# Peripherals.net
KiCad netlist of a schematic drawn in Altium Designer
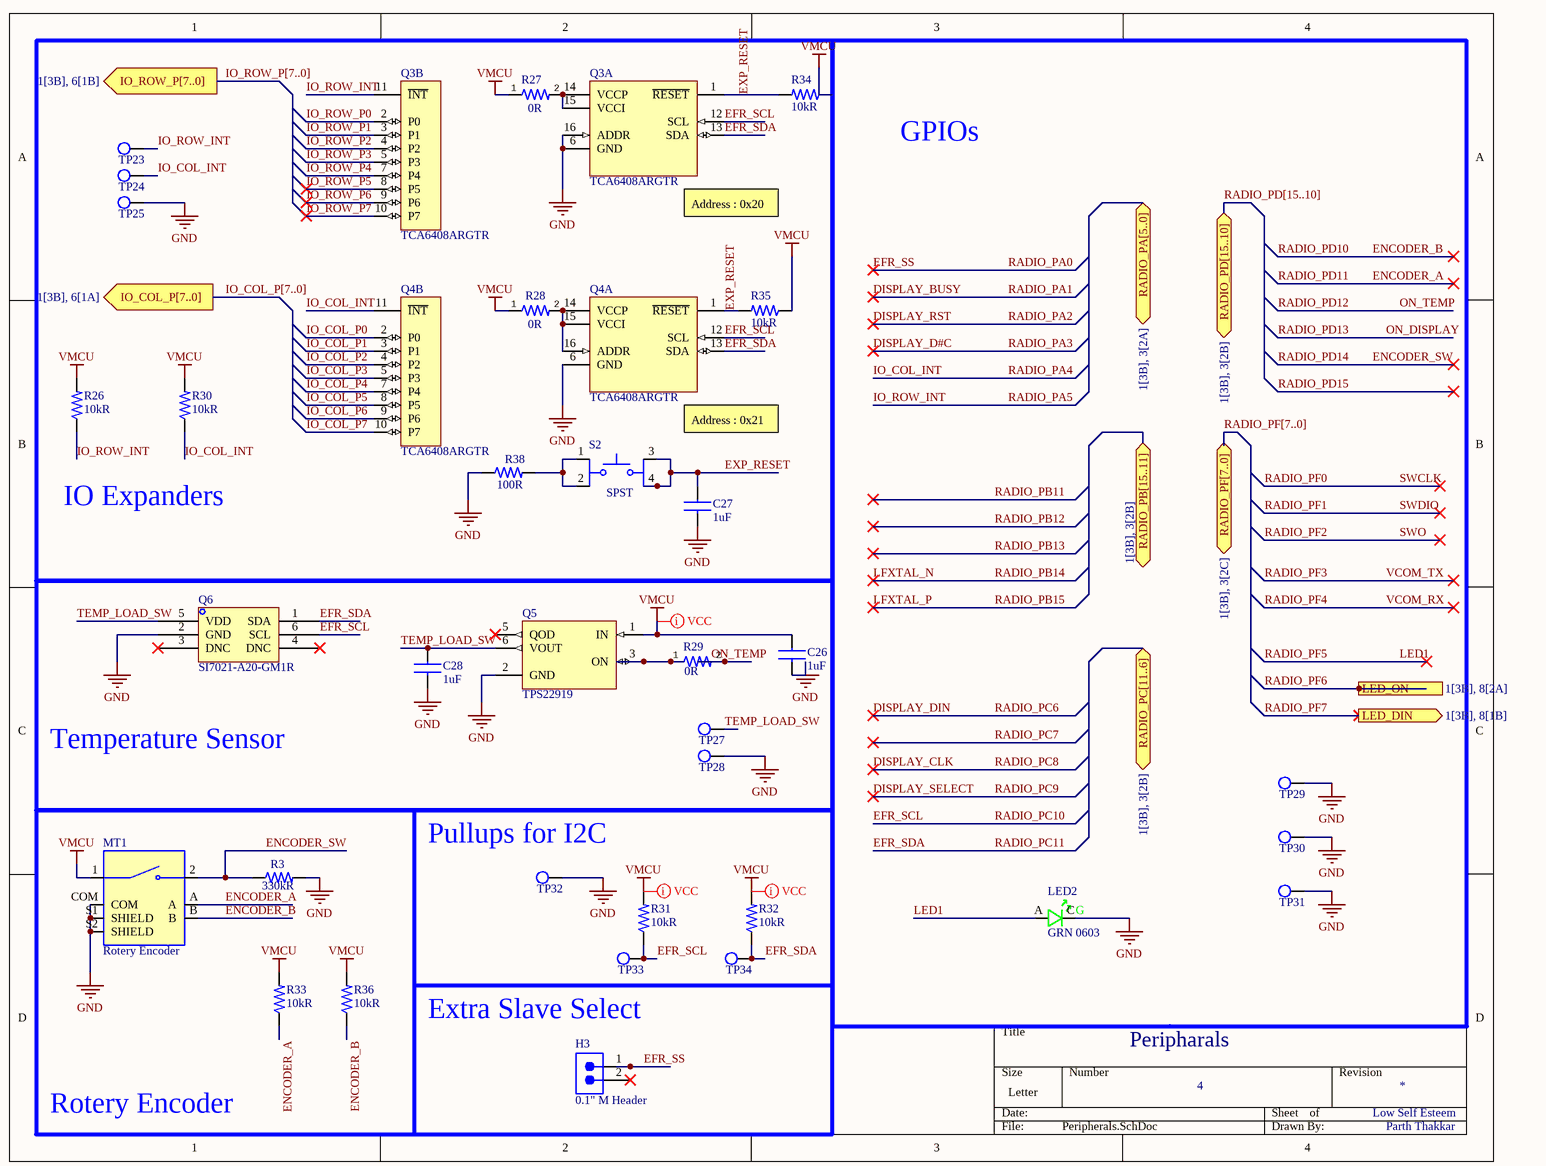
[diagram p0: Peripherals.SchDoc]

(export (version "E")
  (design (tool "Eeschema 10.0.6"))
  (components
    (comp (ref "C26")
      (value "1uF")
      (footprint "Capacitor 0603")
      (fields
        (field (name "MANUFACTURER") "Murata")
        (field (name "MANUFACTURER PART NUMBER") "GRM188R61A105KA61D")
        (field (name "Comment") "CAP 1uF 10V 0603")
      )
      (libsource (lib "Keyboard_parts") (part "CAP 1uF 10V 0603"))
    )
    (comp (ref "C27")
      (value "1uF")
      (footprint "Capacitor 0603")
      (fields
        (field (name "MANUFACTURER") "Murata")
        (field (name "MANUFACTURER PART NUMBER") "GRM188R61A105KA61D")
        (field (name "Comment") "CAP 1uF 10V 0603")
      )
      (libsource (lib "Keyboard_parts") (part "CAP 1uF 10V 0603"))
    )
    (comp (ref "C28")
      (value "1uF")
      (footprint "CAPACITOR 0805")
      (description "Multilayer Ceramic Capacitor, 1 uF, 10 V, ± 20%, X5R, 0201 [0603 Metric]")
      (fields
        (field (name "MANUFACTURER") "Murata")
        (field (name "MANUFACTURER PART NUMBER") "GRM033R61A105ME15D")
      )
      (libsource (lib "Keyboard_parts") (part "CAP 47uF 10V 0805"))
    )
    (comp (ref "H3")
      (value "0.1\" M Header")
      (footprint "2-PIN_MALE_HEADER_01-IN")
      (description "CONN HEADER VERT 2POS 2.54MM")
      (fields
        (field (name "MANUFACTURER") "Sullins")
        (field (name "MANUFACTURER PART NUMBER") "PRPC002SAAN-RC")
      )
      (libsource (lib "InsaneIntegratedLib") (part "PRPC002SAAN-RC"))
    )
    (comp (ref "LED2")
      (value "GRN 0603")
      (footprint "LED 0603")
      (description "LED, 0603, GREEN, 430MCD, 520NM")
      (fields
        (field (name "MANUFACTURER") "Wurth Electronics")
        (field (name "MANUFACTURER PART NUMBER") "150060GS75000")
      )
      (libsource (lib "InsaneIntegratedLib") (part "LED Green 0603"))
    )
    (comp (ref "MT1")
      (value "Rotery Encoder")
      (footprint "Rotery Encoder")
      (description "Rotary Position Encoder, Single, 2 Channels")
      (fields (field (name "MP") "PEC11R-4215F-S0024") (field (name "MANUFACTURER") "Bourns"))
      (libsource (lib "InsaneIntegratedLib") (part "Rotery Encoder"))
    )
    (comp (ref "Q3")
      (value "TCA6408ARGTR")
      (footprint "TCA6408ARGTR - IO Expander")
      (description "Parallel I/O Port, 8-Bit, 8 I/O, CMOS, PQCC16")
      (fields (field (name "MANUFACTURER") "Texas Instruments"))
      (libsource (lib "Keyboard_parts") (part "TCA6408ARGTR"))
    )
    (comp (ref "Q4")
      (value "TCA6408ARGTR")
      (footprint "TCA6408ARGTR - IO Expander")
      (description "Parallel I/O Port, 8-Bit, 8 I/O, CMOS, PQCC16")
      (fields (field (name "MANUFACTURER") "Texas Instruments"))
      (libsource (lib "Keyboard_parts") (part "TCA6408ARGTR"))
    )
    (comp (ref "Q5")
      (value "TPS22919")
      (footprint "TPS22919DCKR - Load SW")
      (description "Buffer/Inverter Based Peripheral Driver, 3A, PDSO6")
      (fields
        (field (name "MANUFACTURER") "Texas Instruments")
        (field (name "MANUFACTURER PART NUMBER") "TPS22919DCKR")
      )
      (libsource (lib "Keyboard_parts") (part "TPS22919"))
    )
    (comp (ref "Q6")
      (value "SI7021-A20-GM1R")
      (footprint "Si7021-A20 - Temp")
      (description "Serial Switch/Digital Sensor, 14 Bit(s), 0.40Cel, Square, Surface Mount")
      (fields (field (name "MANUFACTURER") "Silicon Labs"))
      (libsource (lib "Keyboard_parts") (part "SI7021-A20-GM1R"))
    )
    (comp (ref "R3")
      (value "330kR")
      (footprint "Resistor 0603")
      (fields
        (field (name "MANUFACTURER") "Yageo")
        (field (name "MANUFACTURER PART NUMBER") "RC0603JR-07330KL")
        (field (name "TOLERANCE") "5%")
      )
      (libsource (lib "Keyboard_parts") (part "RES 330K 0603"))
    )
    (comp (ref "R26")
      (value "10kR")
      (footprint "Resistor 0603")
      (fields
        (field (name "MANUFACTURER") "Yageo")
        (field (name "MANUFACTURER PART NUMBER") "RC0603FR-0710KL")
        (field (name "TOLERANCE") "1%")
      )
      (libsource (lib "Keyboard_parts") (part "RES 10K 0603"))
    )
    (comp (ref "R27")
      (value "0R")
      (footprint "Resistor 0402")
      (description "Metal Glaze/thick Film, 0.0625W, 0ohm, Surface Mount, 0402")
      (fields
        (field (name "MANUFACTURER") "Yageo")
        (field (name "MANUFACTURER PART NUMBER") "RC0402JR-070RL")
      )
      (libsource (lib "InsaneIntegratedLib") (part "RES 0R 0402"))
    )
    (comp (ref "R28")
      (value "0R")
      (footprint "Resistor 0402")
      (description "Metal Glaze/thick Film, 0.0625W, 0ohm, Surface Mount, 0402")
      (fields
        (field (name "MANUFACTURER") "Yageo")
        (field (name "MANUFACTURER PART NUMBER") "RC0402JR-070RL")
      )
      (libsource (lib "InsaneIntegratedLib") (part "RES 0R 0402"))
    )
    (comp (ref "R29")
      (value "0R")
      (footprint "Resistor 0402")
      (description "Metal Glaze/thick Film, 0.0625W, 0ohm, Surface Mount, 0402")
      (fields
        (field (name "MANUFACTURER") "Yageo")
        (field (name "MANUFACTURER PART NUMBER") "RC0402JR-070RL")
      )
      (libsource (lib "InsaneIntegratedLib") (part "RES 0R 0402"))
    )
    (comp (ref "R30")
      (value "10kR")
      (footprint "Resistor 0603")
      (fields
        (field (name "MANUFACTURER") "Yageo")
        (field (name "MANUFACTURER PART NUMBER") "RC0603FR-0710KL")
        (field (name "TOLERANCE") "1%")
      )
      (libsource (lib "Keyboard_parts") (part "RES 10K 0603"))
    )
    (comp (ref "R31")
      (value "10kR")
      (footprint "Resistor 0603")
      (fields
        (field (name "MANUFACTURER") "Yageo")
        (field (name "MANUFACTURER PART NUMBER") "RC0603FR-0710KL")
        (field (name "TOLERANCE") "1%")
      )
      (libsource (lib "Keyboard_parts") (part "RES 10K 0603"))
    )
    (comp (ref "R32")
      (value "10kR")
      (footprint "Resistor 0603")
      (fields
        (field (name "MANUFACTURER") "Yageo")
        (field (name "MANUFACTURER PART NUMBER") "RC0603FR-0710KL")
        (field (name "TOLERANCE") "1%")
      )
      (libsource (lib "Keyboard_parts") (part "RES 10K 0603"))
    )
    (comp (ref "R33")
      (value "10kR")
      (footprint "Resistor 0603")
      (fields
        (field (name "MANUFACTURER") "Yageo")
        (field (name "MANUFACTURER PART NUMBER") "RC0603FR-0710KL")
        (field (name "TOLERANCE") "1%")
      )
      (libsource (lib "Keyboard_parts") (part "RES 10K 0603"))
    )
    (comp (ref "R34")
      (value "10kR")
      (footprint "Resistor 0603")
      (fields
        (field (name "MANUFACTURER") "Yageo")
        (field (name "MANUFACTURER PART NUMBER") "RC0603FR-0710KL")
        (field (name "TOLERANCE") "1%")
      )
      (libsource (lib "Keyboard_parts") (part "RES 10K 0603"))
    )
    (comp (ref "R35")
      (value "10kR")
      (footprint "Resistor 0603")
      (fields
        (field (name "MANUFACTURER") "Yageo")
        (field (name "MANUFACTURER PART NUMBER") "RC0603FR-0710KL")
        (field (name "TOLERANCE") "1%")
      )
      (libsource (lib "Keyboard_parts") (part "RES 10K 0603"))
    )
    (comp (ref "R36")
      (value "10kR")
      (footprint "Resistor 0603")
      (fields
        (field (name "MANUFACTURER") "Yageo")
        (field (name "MANUFACTURER PART NUMBER") "RC0603FR-0710KL")
        (field (name "TOLERANCE") "1%")
      )
      (libsource (lib "Keyboard_parts") (part "RES 10K 0603"))
    )
    (comp (ref "R38")
      (value "100R")
      (footprint "Resistor 0603")
      (fields
        (field (name "MANUFACTURER") "Yageo")
        (field (name "MANUFACTURER PART NUMBER") "RC0603FR-07100RL")
        (field (name "TOLERANCE") "1%")
      )
      (libsource (lib "Keyboard_parts") (part "RES 100R 0603"))
    )
    (comp (ref "S2")
      (value "SPST")
      (footprint "SPST")
      (fields
        (field (name "MANUFACTURER") "E-Switch")
        (field (name "MANUFACTURER PART NUMBER") "TL3301NF260QG")
      )
      (libsource (lib "Keyboard_parts") (part "SPST"))
    )
    (comp (ref "TP23")
      (value "Test point")
      (footprint "Test Point")
      (libsource (lib "Keyboard_parts") (part "Test point"))
    )
    (comp (ref "TP24")
      (value "Test point")
      (footprint "Test Point")
      (libsource (lib "Keyboard_parts") (part "Test point"))
    )
    (comp (ref "TP25")
      (value "Test point")
      (footprint "Test Point")
      (libsource (lib "Keyboard_parts") (part "Test point"))
    )
    (comp (ref "TP27")
      (value "Test point")
      (footprint "Test Point")
      (libsource (lib "Keyboard_parts") (part "Test point"))
    )
    (comp (ref "TP28")
      (value "Test point")
      (footprint "Test Point")
      (libsource (lib "Keyboard_parts") (part "Test point"))
    )
    (comp (ref "TP29")
      (value "Test point")
      (footprint "Test Point")
      (libsource (lib "Keyboard_parts") (part "Test point"))
    )
    (comp (ref "TP30")
      (value "Test point")
      (footprint "Test Point")
      (libsource (lib "Keyboard_parts") (part "Test point"))
    )
    (comp (ref "TP31")
      (value "Test point")
      (footprint "Test Point")
      (libsource (lib "Keyboard_parts") (part "Test point"))
    )
    (comp (ref "TP32")
      (value "Test point")
      (footprint "Test Point")
      (libsource (lib "Keyboard_parts") (part "Test point"))
    )
    (comp (ref "TP33")
      (value "Test point")
      (footprint "Test Point")
      (libsource (lib "Keyboard_parts") (part "Test point"))
    )
    (comp (ref "TP34")
      (value "Test point")
      (footprint "Test Point")
      (libsource (lib "Keyboard_parts") (part "Test point"))
    )
  )
  (nets
    (net (code "1") (name "/EXP_RESET") (class "Default")
      (node (ref "C27") (pin "1") (pinfunction "1_1") (pintype "passive"))
      (node (ref "Q3") (pin "1") (pinfunction "~{RESET}_1") (pintype "passive"))
      (node (ref "Q4") (pin "1") (pinfunction "~{RESET}_1") (pintype "passive"))
      (node (ref "R34") (pin "2") (pinfunction "2_2") (pintype "passive"))
      (node (ref "R35") (pin "2") (pinfunction "2_2") (pintype "passive"))
      (node (ref "S2") (pin "3") (pinfunction "3_3") (pintype "passive"))
      (node (ref "S2") (pin "4") (pinfunction "4_4") (pintype "passive"))
    )
    (net (code "2") (name "/IO_COL_P0") (class "Default")
      (node (ref "Q4") (pin "2") (pinfunction "P0_2") (pintype "bidirectional"))
    )
    (net (code "3") (name "/IO_COL_P1") (class "Default")
      (node (ref "Q4") (pin "3") (pinfunction "P1_3") (pintype "bidirectional"))
    )
    (net (code "4") (name "/IO_COL_P2") (class "Default")
      (node (ref "Q4") (pin "4") (pinfunction "P2_4") (pintype "bidirectional"))
    )
    (net (code "5") (name "/IO_COL_P3") (class "Default")
      (node (ref "Q4") (pin "5") (pinfunction "P3_5") (pintype "bidirectional"))
    )
    (net (code "6") (name "/IO_COL_P4") (class "Default")
      (node (ref "Q4") (pin "7") (pinfunction "P4_7") (pintype "bidirectional"))
    )
    (net (code "7") (name "/IO_COL_P5") (class "Default")
      (node (ref "Q4") (pin "8") (pinfunction "P5_8") (pintype "bidirectional"))
    )
    (net (code "8") (name "/IO_COL_P6") (class "Default")
      (node (ref "Q4") (pin "9") (pinfunction "P6_9") (pintype "bidirectional"))
    )
    (net (code "9") (name "/IO_COL_P7") (class "Default")
      (node (ref "Q4") (pin "10") (pinfunction "P7_10") (pintype "bidirectional"))
    )
    (net (code "11") (name "/IO_ROW_P0") (class "Default")
      (node (ref "Q3") (pin "2") (pinfunction "P0_2") (pintype "bidirectional"))
    )
    (net (code "12") (name "/IO_ROW_P1") (class "Default")
      (node (ref "Q3") (pin "3") (pinfunction "P1_3") (pintype "bidirectional"))
    )
    (net (code "13") (name "/IO_ROW_P2") (class "Default")
      (node (ref "Q3") (pin "4") (pinfunction "P2_4") (pintype "bidirectional"))
    )
    (net (code "14") (name "/IO_ROW_P3") (class "Default")
      (node (ref "Q3") (pin "5") (pinfunction "P3_5") (pintype "bidirectional"))
    )
    (net (code "15") (name "/IO_ROW_P4") (class "Default")
      (node (ref "Q3") (pin "7") (pinfunction "P4_7") (pintype "bidirectional"))
    )
    (net (code "16") (name "/IO_ROW_P5") (class "Default")
      (node (ref "Q3") (pin "8") (pinfunction "P5_8") (pintype "bidirectional+no_connect"))
    )
    (net (code "17") (name "/IO_ROW_P6") (class "Default")
      (node (ref "Q3") (pin "9") (pinfunction "P6_9") (pintype "bidirectional+no_connect"))
    )
    (net (code "18") (name "/IO_ROW_P7") (class "Default")
      (node (ref "Q3") (pin "10") (pinfunction "P7_10") (pintype "bidirectional+no_connect"))
    )
    (net (code "20") (name "/RADIO_PA0") (class "Default")
      (node (ref "H3") (pin "1") (pinfunction "1_1") (pintype "passive"))
    )
    (net (code "24") (name "/RADIO_PA4") (class "Default")
      (node (ref "Q4") (pin "11") (pinfunction "~{INT}_11") (pintype "passive"))
      (node (ref "R30") (pin "1") (pinfunction "1_1") (pintype "passive"))
      (node (ref "TP24") (pin "1") (pinfunction "1_1") (pintype "passive"))
    )
    (net (code "25") (name "/RADIO_PA5") (class "Default")
      (node (ref "Q3") (pin "11") (pinfunction "~{INT}_11") (pintype "passive"))
      (node (ref "R26") (pin "1") (pinfunction "1_1") (pintype "passive"))
      (node (ref "TP23") (pin "1") (pinfunction "1_1") (pintype "passive"))
    )
    (net (code "37") (name "/RADIO_PC10") (class "Default")
      (node (ref "Q3") (pin "12") (pinfunction "SCL_12") (pintype "input"))
      (node (ref "Q4") (pin "12") (pinfunction "SCL_12") (pintype "input"))
      (node (ref "Q6") (pin "6") (pinfunction "SCL_6") (pintype "passive"))
      (node (ref "R31") (pin "1") (pinfunction "1_1") (pintype "passive"))
      (node (ref "TP33") (pin "1") (pinfunction "1_1") (pintype "passive"))
    )
    (net (code "38") (name "/RADIO_PC11") (class "Default")
      (node (ref "Q3") (pin "13") (pinfunction "SDA_13") (pintype "bidirectional"))
      (node (ref "Q4") (pin "13") (pinfunction "SDA_13") (pintype "bidirectional"))
      (node (ref "Q6") (pin "1") (pinfunction "SDA_1") (pintype "passive"))
      (node (ref "R32") (pin "1") (pinfunction "1_1") (pintype "passive"))
      (node (ref "TP34") (pin "1") (pinfunction "1_1") (pintype "passive"))
    )
    (net (code "40") (name "/RADIO_PD10") (class "Default")
      (node (ref "MT1") (pin "B") (pinfunction "B_B") (pintype "passive"))
      (node (ref "R36") (pin "1") (pinfunction "1_1") (pintype "passive"))
    )
    (net (code "41") (name "/RADIO_PD11") (class "Default")
      (node (ref "MT1") (pin "A") (pinfunction "A_A") (pintype "passive"))
      (node (ref "R33") (pin "1") (pinfunction "1_1") (pintype "passive"))
    )
    (net (code "42") (name "/RADIO_PD12") (class "Default")
      (node (ref "R29") (pin "2") (pinfunction "2_2") (pintype "passive"))
    )
    (net (code "44") (name "/RADIO_PD14") (class "Default")
      (node (ref "MT1") (pin "2") (pinfunction "2_2") (pintype "passive"))
      (node (ref "R3") (pin "1") (pinfunction "1_1") (pintype "passive"))
    )
    (net (code "52") (name "/RADIO_PF5") (class "Default")
      (node (ref "LED2") (pin "A") (pinfunction "A_A") (pintype "passive"))
    )
    (net (code "56") (name "/TEMP_LOAD_SW") (class "Default")
      (node (ref "C28") (pin "1") (pinfunction "1_1") (pintype "passive"))
      (node (ref "Q5") (pin "6") (pinfunction "VOUT_6") (pintype "output"))
      (node (ref "Q6") (pin "5") (pinfunction "VDD_5") (pintype "passive"))
      (node (ref "TP27") (pin "1") (pinfunction "1_1") (pintype "passive"))
    )
    (net (code "57") (name "GND") (class "Default")
      (node (ref "C26") (pin "2") (pinfunction "2_2") (pintype "passive"))
      (node (ref "C27") (pin "2") (pinfunction "2_2") (pintype "passive"))
      (node (ref "C28") (pin "2") (pinfunction "2_2") (pintype "passive"))
      (node (ref "LED2") (pin "C") (pinfunction "C_C") (pintype "passive"))
      (node (ref "MT1") (pin "COM") (pinfunction "COM_COM") (pintype "passive"))
      (node (ref "MT1") (pin "S1") (pinfunction "SHIELD_S1") (pintype "passive"))
      (node (ref "MT1") (pin "S2") (pinfunction "SHIELD_S2") (pintype "passive"))
      (node (ref "Q3") (pin "16") (pinfunction "ADDR_16") (pintype "input"))
      (node (ref "Q3") (pin "6") (pinfunction "GND_6") (pintype "passive"))
      (node (ref "Q4") (pin "6") (pinfunction "GND_6") (pintype "passive"))
      (node (ref "Q5") (pin "2") (pinfunction "GND_2") (pintype "power_in"))
      (node (ref "Q6") (pin "2") (pinfunction "GND_2") (pintype "passive"))
      (node (ref "R3") (pin "2") (pinfunction "2_2") (pintype "passive"))
      (node (ref "R38") (pin "1") (pinfunction "1_1") (pintype "passive"))
      (node (ref "TP25") (pin "1") (pinfunction "1_1") (pintype "passive"))
      (node (ref "TP28") (pin "1") (pinfunction "1_1") (pintype "passive"))
      (node (ref "TP29") (pin "1") (pinfunction "1_1") (pintype "passive"))
      (node (ref "TP30") (pin "1") (pinfunction "1_1") (pintype "passive"))
      (node (ref "TP31") (pin "1") (pinfunction "1_1") (pintype "passive"))
      (node (ref "TP32") (pin "1") (pinfunction "1_1") (pintype "passive"))
    )
    (net (code "58") (name "Net-(Q3A-VCCI)") (class "Default")
      (node (ref "Q3") (pin "14") (pinfunction "VCCP_14") (pintype "power_in"))
      (node (ref "Q3") (pin "15") (pinfunction "VCCI_15") (pintype "power_in"))
      (node (ref "R27") (pin "2") (pinfunction "2_2") (pintype "passive"))
    )
    (net (code "59") (name "Net-(Q4A-ADDR)") (class "Default")
      (node (ref "Q4") (pin "14") (pinfunction "VCCP_14") (pintype "power_in"))
      (node (ref "Q4") (pin "15") (pinfunction "VCCI_15") (pintype "power_in"))
      (node (ref "Q4") (pin "16") (pinfunction "ADDR_16") (pintype "input"))
      (node (ref "R28") (pin "2") (pinfunction "2_2") (pintype "passive"))
    )
    (net (code "60") (name "Net-(Q5-ON)") (class "Default")
      (node (ref "Q5") (pin "3") (pinfunction "ON_3") (pintype "bidirectional"))
      (node (ref "R29") (pin "1") (pinfunction "1_1") (pintype "passive"))
    )
    (net (code "61") (name "Net-(R38-Pad2)") (class "Default")
      (node (ref "R38") (pin "2") (pinfunction "2_2") (pintype "passive"))
      (node (ref "S2") (pin "1") (pinfunction "1_1") (pintype "passive"))
      (node (ref "S2") (pin "2") (pinfunction "2_2") (pintype "passive"))
    )
    (net (code "62") (name "VMCU") (class "Default")
      (node (ref "C26") (pin "1") (pinfunction "1_1") (pintype "passive"))
      (node (ref "MT1") (pin "1") (pinfunction "1_1") (pintype "passive"))
      (node (ref "Q5") (pin "1") (pinfunction "IN_1") (pintype "input"))
      (node (ref "R26") (pin "2") (pinfunction "2_2") (pintype "passive"))
      (node (ref "R27") (pin "1") (pinfunction "1_1") (pintype "passive"))
      (node (ref "R28") (pin "1") (pinfunction "1_1") (pintype "passive"))
      (node (ref "R30") (pin "2") (pinfunction "2_2") (pintype "passive"))
      (node (ref "R31") (pin "2") (pinfunction "2_2") (pintype "passive"))
      (node (ref "R32") (pin "2") (pinfunction "2_2") (pintype "passive"))
      (node (ref "R33") (pin "2") (pinfunction "2_2") (pintype "passive"))
      (node (ref "R34") (pin "1") (pinfunction "1_1") (pintype "passive"))
      (node (ref "R35") (pin "1") (pinfunction "1_1") (pintype "passive"))
      (node (ref "R36") (pin "2") (pinfunction "2_2") (pintype "passive"))
    )
    (net (code "63") (name "unconnected-(H3-Pad2)") (class "Default")
      (node (ref "H3") (pin "2") (pinfunction "2_2") (pintype "passive+no_connect"))
    )
    (net (code "64") (name "unconnected-(Q5-QOD-Pad5)") (class "Default")
      (node (ref "Q5") (pin "5") (pinfunction "QOD_5") (pintype "output+no_connect"))
    )
    (net (code "65") (name "unconnected-(Q6-DNC-Pad3)") (class "Default")
      (node (ref "Q6") (pin "3") (pinfunction "DNC_3") (pintype "passive+no_connect"))
    )
    (net (code "66") (name "unconnected-(Q6-DNC-Pad4)") (class "Default")
      (node (ref "Q6") (pin "4") (pinfunction "DNC_4") (pintype "passive+no_connect"))
    )
  )
)
